# Qwiic_Joystick.net
KiCad netlist of a schematic drawn in EAGLE
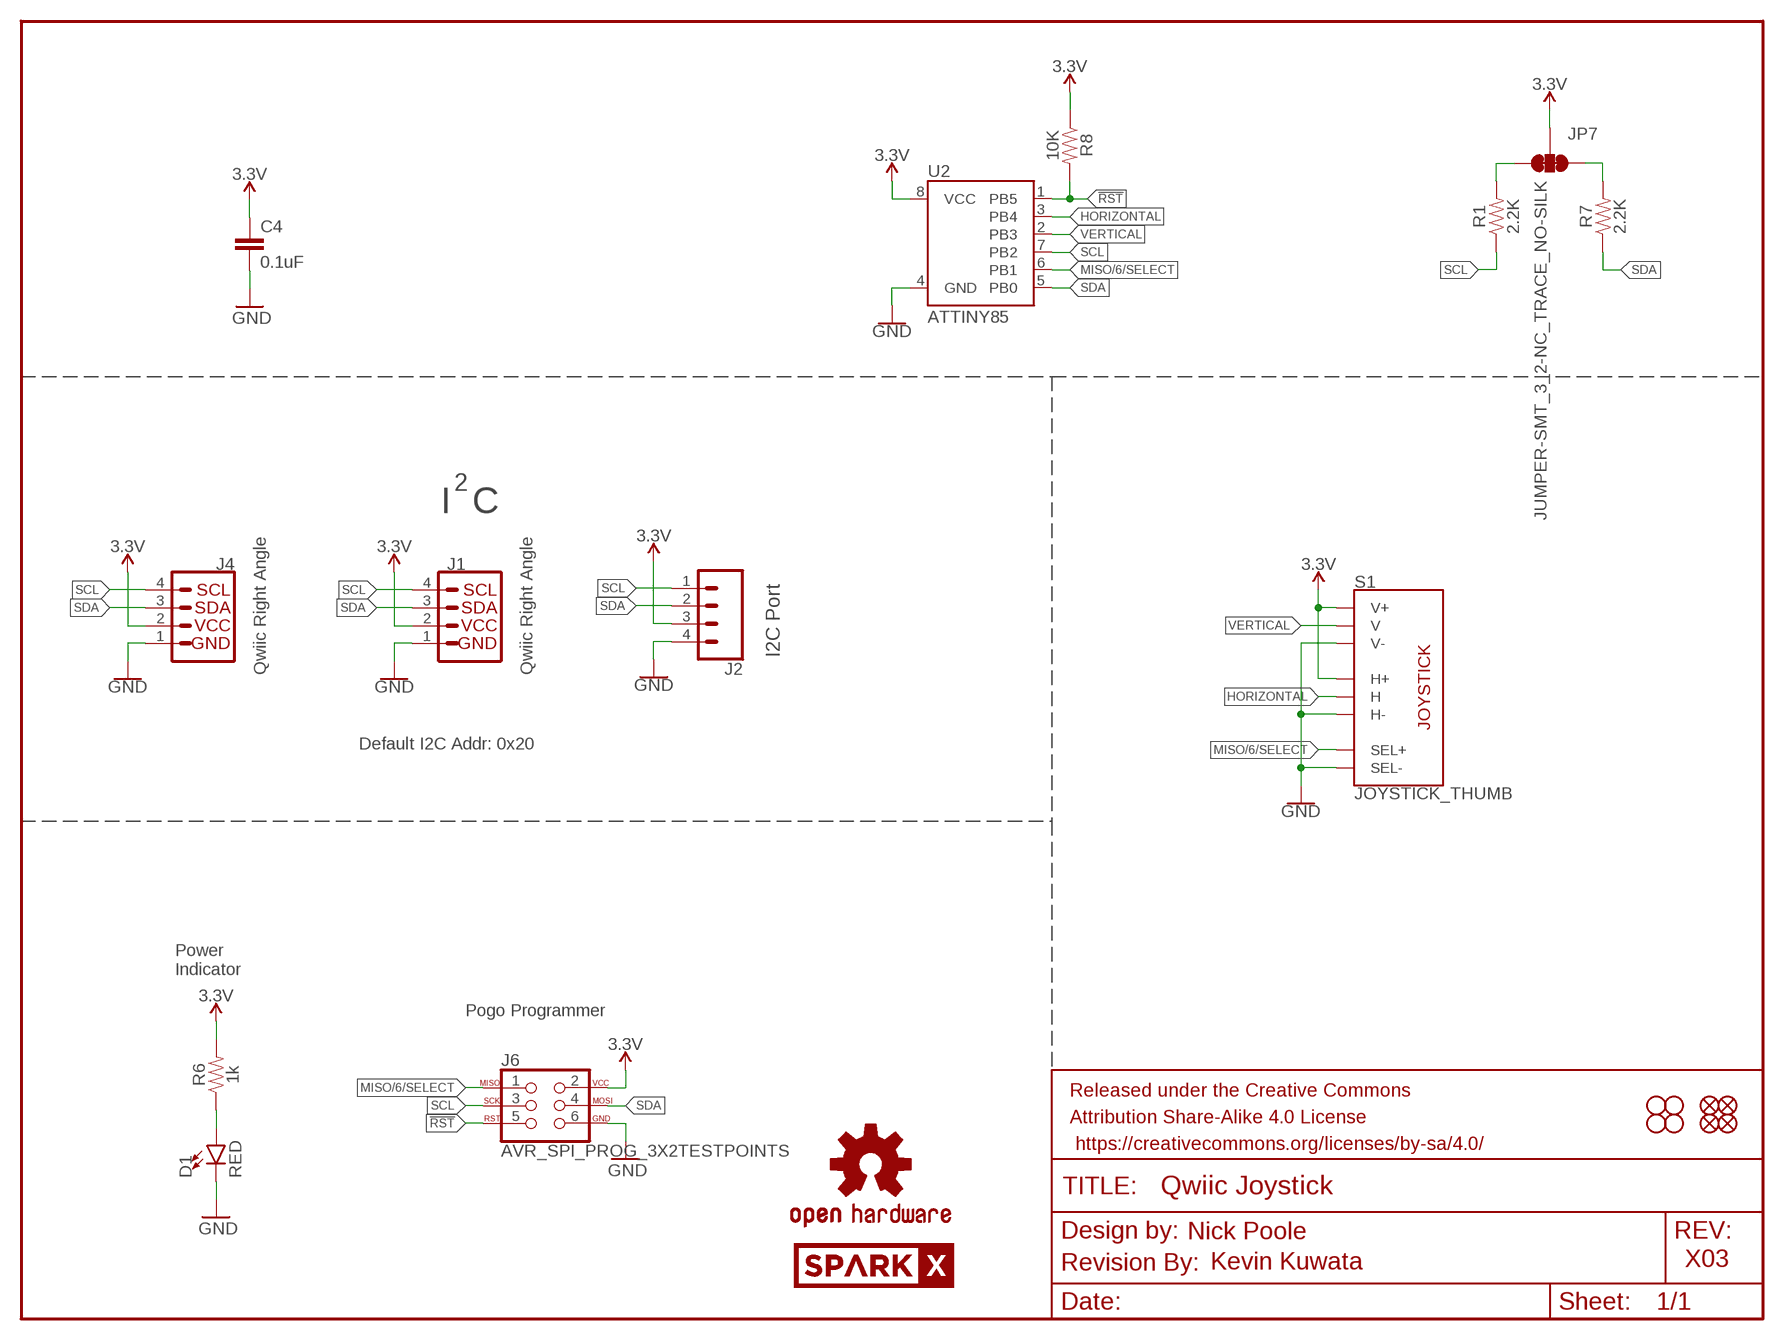
[diagram p0: schematic, sheet 1]

(export (version "E")
  (design (tool "Eeschema 10.0.6"))
  (components
    (comp (ref "C4")
      (value "0.1uF")
      (footprint "eagle-import:0603")
      (libsource (lib "eagle-import") (part "0.1UF-0603-25V-(+80/-20%)"))
    )
    (comp (ref "D1")
      (value "RED")
      (footprint "eagle-import:LED-0603")
      (libsource (lib "eagle-import") (part "LED-RED0603"))
    )
    (comp (ref "FRAME1")
      (value "FRAME-LETTER")
      (footprint "eagle-import:CREATIVE_COMMONS")
      (libsource (lib "eagle-import") (part "FRAME-LETTER"))
    )
    (comp (ref "H1")
      (value "STAND-OFF")
      (footprint "eagle-import:STAND-OFF")
      (libsource (lib "eagle-import") (part "STAND-OFF"))
    )
    (comp (ref "H2")
      (value "STAND-OFF")
      (footprint "eagle-import:STAND-OFF")
      (libsource (lib "eagle-import") (part "STAND-OFF"))
    )
    (comp (ref "H3")
      (value "STAND-OFF")
      (footprint "eagle-import:STAND-OFF")
      (libsource (lib "eagle-import") (part "STAND-OFF"))
    )
    (comp (ref "H4")
      (value "STAND-OFF")
      (footprint "eagle-import:STAND-OFF")
      (libsource (lib "eagle-import") (part "STAND-OFF"))
    )
    (comp (ref "J1")
      (value "Qwiic Right Angle")
      (footprint "eagle-import:1X04_1MM_RA")
      (libsource (lib "eagle-import") (part "I2C_STANDARDQWIIC"))
    )
    (comp (ref "J2")
      (value "CONN_041X04_NO_SILK")
      (footprint "eagle-import:1X04_NO_SILK")
      (libsource (lib "eagle-import") (part "CONN_041X04_NO_SILK"))
    )
    (comp (ref "J4")
      (value "Qwiic Right Angle")
      (footprint "eagle-import:1X04_1MM_RA")
      (libsource (lib "eagle-import") (part "I2C_STANDARDQWIIC"))
    )
    (comp (ref "J6")
      (value "AVR_SPI_PROG_3X2TESTPOINTS")
      (footprint "eagle-import:2X3_TEST_POINTS")
      (libsource (lib "eagle-import") (part "AVR_SPI_PROG_3X2TESTPOINTS"))
    )
    (comp (ref "JP1")
      (value "FIDUCIALUFIDUCIAL")
      (footprint "eagle-import:MICRO-FIDUCIAL")
      (libsource (lib "eagle-import") (part "FIDUCIALUFIDUCIAL"))
    )
    (comp (ref "JP2")
      (value "FIDUCIALUFIDUCIAL")
      (footprint "eagle-import:MICRO-FIDUCIAL")
      (libsource (lib "eagle-import") (part "FIDUCIALUFIDUCIAL"))
    )
    (comp (ref "JP3")
      (value "FIDUCIALUFIDUCIAL")
      (footprint "eagle-import:MICRO-FIDUCIAL")
      (libsource (lib "eagle-import") (part "FIDUCIALUFIDUCIAL"))
    )
    (comp (ref "JP6")
      (value "FIDUCIALUFIDUCIAL")
      (footprint "eagle-import:MICRO-FIDUCIAL")
      (libsource (lib "eagle-import") (part "FIDUCIALUFIDUCIAL"))
    )
    (comp (ref "JP7")
      (value "JUMPER-SMT_3_2-NC_TRACE_NO-SILK")
      (footprint "eagle-import:SMT-JUMPER_3_2-NC_TRACE_NO-SILK")
      (libsource (lib "eagle-import") (part "JUMPER-SMT_3_2-NC_TRACE_NO-SILK"))
    )
    (comp (ref "LOGO1")
      (value "OSHW-LOGOMINI")
      (footprint "eagle-import:OSHW-LOGO-MINI")
      (libsource (lib "eagle-import") (part "OSHW-LOGOMINI"))
    )
    (comp (ref "LOGO2")
      (value "REVISION")
      (footprint "eagle-import:REVISION")
      (libsource (lib "eagle-import") (part "REVISION"))
    )
    (comp (ref "R1")
      (value "2.2K")
      (footprint "eagle-import:0603")
      (libsource (lib "eagle-import") (part "4.7KOHM-0603-1/10W-1%"))
    )
    (comp (ref "R6")
      (value "1k")
      (footprint "eagle-import:0603")
      (libsource (lib "eagle-import") (part "1KOHM-0603-1/10W-1%"))
    )
    (comp (ref "R7")
      (value "2.2K")
      (footprint "eagle-import:0603")
      (libsource (lib "eagle-import") (part "4.7KOHM-0603-1/10W-1%"))
    )
    (comp (ref "R8")
      (value "10K")
      (footprint "eagle-import:0603")
      (libsource (lib "eagle-import") (part "330OHM-0603-1/10W-1%"))
    )
    (comp (ref "S1")
      (value "JOYSTICK_THUMB")
      (footprint "eagle-import:JOYSTICK")
      (libsource (lib "eagle-import") (part "JOYSTICK_THUMB"))
    )
    (comp (ref "U$1")
      (value "SPARKX-LOGO3")
      (footprint "eagle-import:SPARKX-SMALL")
      (libsource (lib "eagle-import") (part "SPARKX-LOGO3"))
    )
    (comp (ref "U$2")
      (value "SPARKX-LOGO3")
      (footprint "eagle-import:SPARKX-SMALL")
      (libsource (lib "eagle-import") (part "SPARKX-LOGO3"))
    )
    (comp (ref "U2")
      (value "ATTINY85")
      (footprint "eagle-import:ATTINY85")
      (libsource (lib "eagle-import") (part "ATTINY85"))
    )
  )
  (nets
    (net (code "1") (name "/~{RST}") (class "Default")
      (node (ref "J6") (pin "5") (pinfunction "5_5") (pintype "passive"))
      (node (ref "R8") (pin "2") (pinfunction "2_2") (pintype "passive"))
      (node (ref "U2") (pin "1") (pinfunction "PB5_1") (pintype "bidirectional"))
    )
    (net (code "2") (name "3.3V") (class "Default")
      (node (ref "C4") (pin "1") (pinfunction "1_1") (pintype "passive"))
      (node (ref "J1") (pin "2") (pinfunction "2_2") (pintype "power_in"))
      (node (ref "J2") (pin "3") (pinfunction "3_3") (pintype "passive"))
      (node (ref "J4") (pin "2") (pinfunction "2_2") (pintype "power_in"))
      (node (ref "J6") (pin "2") (pinfunction "2_2") (pintype "passive"))
      (node (ref "JP7") (pin "2") (pinfunction "2_2") (pintype "passive"))
      (node (ref "R6") (pin "2") (pinfunction "2_2") (pintype "passive"))
      (node (ref "R8") (pin "1") (pinfunction "1_1") (pintype "passive"))
      (node (ref "S1") (pin "H1") (pinfunction "H+_H1") (pintype "bidirectional"))
      (node (ref "S1") (pin "V1") (pinfunction "V+_V1") (pintype "bidirectional"))
      (node (ref "U2") (pin "8") (pinfunction "VCC_8") (pintype "bidirectional"))
    )
    (net (code "3") (name "GND") (class "Default")
      (node (ref "C4") (pin "2") (pinfunction "2_2") (pintype "passive"))
      (node (ref "D1") (pin "C") (pinfunction "C_C") (pintype "passive"))
      (node (ref "J1") (pin "1") (pinfunction "1_1") (pintype "power_in"))
      (node (ref "J2") (pin "4") (pinfunction "4_4") (pintype "passive"))
      (node (ref "J4") (pin "1") (pinfunction "1_1") (pintype "power_in"))
      (node (ref "J6") (pin "6") (pinfunction "6_6") (pintype "passive"))
      (node (ref "S1") (pin "B2A") (pinfunction "SEL-_B2A") (pintype "bidirectional"))
      (node (ref "S1") (pin "H3") (pinfunction "H-_H3") (pintype "bidirectional"))
      (node (ref "S1") (pin "V3") (pinfunction "V-_V3") (pintype "bidirectional"))
      (node (ref "U2") (pin "4") (pinfunction "GND_4") (pintype "bidirectional"))
    )
    (net (code "4") (name "HORIZONTAL") (class "Default")
      (node (ref "S1") (pin "H2") (pinfunction "H_H2") (pintype "bidirectional"))
      (node (ref "U2") (pin "3") (pinfunction "PB4_3") (pintype "bidirectional"))
    )
    (net (code "5") (name "MISO{slash}6{slash}SELECT") (class "Default")
      (node (ref "J6") (pin "1") (pinfunction "1_1") (pintype "passive"))
      (node (ref "S1") (pin "B1A") (pinfunction "SEL+_B1A") (pintype "bidirectional"))
      (node (ref "U2") (pin "6") (pinfunction "PB1_6") (pintype "bidirectional"))
    )
    (net (code "6") (name "Net-(D1-PadA)") (class "Default")
      (node (ref "D1") (pin "A") (pinfunction "A_A") (pintype "passive"))
      (node (ref "R6") (pin "1") (pinfunction "1_1") (pintype "passive"))
    )
    (net (code "7") (name "Net-(JP7-Pad1)") (class "Default")
      (node (ref "JP7") (pin "1") (pinfunction "1_1") (pintype "passive"))
      (node (ref "R7") (pin "2") (pinfunction "2_2") (pintype "passive"))
    )
    (net (code "8") (name "Net-(JP7-Pad3)") (class "Default")
      (node (ref "JP7") (pin "3") (pinfunction "3_3") (pintype "passive"))
      (node (ref "R1") (pin "2") (pinfunction "2_2") (pintype "passive"))
    )
    (net (code "9") (name "SCL") (class "Default")
      (node (ref "J1") (pin "4") (pinfunction "4_4") (pintype "passive"))
      (node (ref "J2") (pin "1") (pinfunction "1_1") (pintype "passive"))
      (node (ref "J4") (pin "4") (pinfunction "4_4") (pintype "passive"))
      (node (ref "J6") (pin "3") (pinfunction "3_3") (pintype "passive"))
      (node (ref "R1") (pin "1") (pinfunction "1_1") (pintype "passive"))
      (node (ref "U2") (pin "7") (pinfunction "PB2_7") (pintype "bidirectional"))
    )
    (net (code "10") (name "SDA") (class "Default")
      (node (ref "J1") (pin "3") (pinfunction "3_3") (pintype "passive"))
      (node (ref "J2") (pin "2") (pinfunction "2_2") (pintype "passive"))
      (node (ref "J4") (pin "3") (pinfunction "3_3") (pintype "passive"))
      (node (ref "J6") (pin "4") (pinfunction "4_4") (pintype "passive"))
      (node (ref "R7") (pin "1") (pinfunction "1_1") (pintype "passive"))
      (node (ref "U2") (pin "5") (pinfunction "PB0_5") (pintype "bidirectional"))
    )
    (net (code "11") (name "VERTICAL") (class "Default")
      (node (ref "S1") (pin "V2") (pinfunction "V_V2") (pintype "bidirectional"))
      (node (ref "U2") (pin "2") (pinfunction "PB3_2") (pintype "bidirectional"))
    )
  )
)
